# NIBB.net
KiCad netlist of a schematic drawn in EAGLE
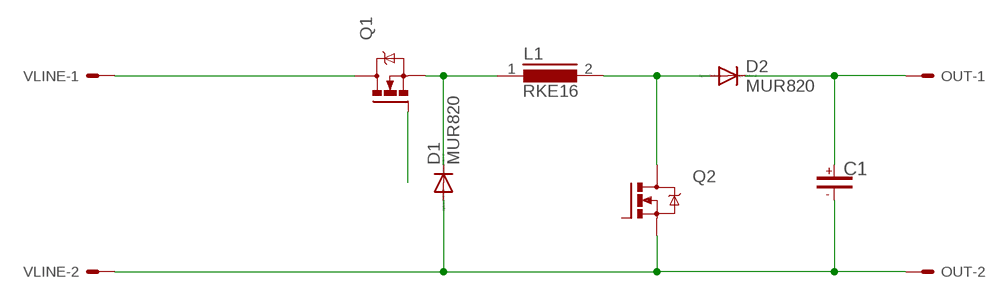
[diagram p0: schematic, sheet 1]

(export (version "E")
  (design (tool "Eeschema 10.0.6"))
  (components
    (comp (ref "C1")
      (value "CAPP-UF")
      (footprint "eagle-import:20ROUND40P")
      (libsource (lib "eagle-import") (part "CAPP-UF"))
    )
    (comp (ref "D1")
      (value "MUR820")
      (footprint "eagle-import:C221B1A")
      (libsource (lib "eagle-import") (part "MUR820"))
    )
    (comp (ref "D2")
      (value "MUR820")
      (footprint "eagle-import:C221B1A")
      (libsource (lib "eagle-import") (part "MUR820"))
    )
    (comp (ref "L1")
      (value "RKE16")
      (footprint "eagle-import:RKE16")
      (libsource (lib "eagle-import") (part "RKE16"))
    )
    (comp (ref "OUT")
      (value "22-23-2021")
      (footprint "eagle-import:22-23-2021")
      (fields (field (name "MF") "MOLEX"))
      (libsource (lib "eagle-import") (part "22-23-2021"))
    )
    (comp (ref "Q1")
      (value "IRF640")
      (footprint "eagle-import:TO220BV")
      (libsource (lib "eagle-import") (part "IRF640"))
    )
    (comp (ref "Q2")
      (value "IRF640")
      (footprint "eagle-import:TO220BV")
      (libsource (lib "eagle-import") (part "IRF640"))
    )
    (comp (ref "VLINE")
      (value "22-23-2021")
      (footprint "eagle-import:22-23-2021")
      (fields (field (name "MF") "MOLEX"))
      (libsource (lib "eagle-import") (part "22-23-2021"))
    )
  )
  (nets
    (net (code "1") (name "Net-(D1-PadC)") (class "Default")
      (node (ref "D1") (pin "C") (pinfunction "C_C") (pintype "passive"))
      (node (ref "L1") (pin "1") (pinfunction "1_1") (pintype "passive"))
      (node (ref "Q1") (pin "S") (pinfunction "S_S") (pintype "passive"))
    )
    (net (code "2") (name "Net-(D2-PadA)") (class "Default")
      (node (ref "D2") (pin "A") (pinfunction "A_A") (pintype "passive"))
      (node (ref "L1") (pin "2") (pinfunction "2_2") (pintype "passive"))
      (node (ref "Q2") (pin "D") (pinfunction "D_D") (pintype "passive"))
    )
    (net (code "3") (name "Net-(OUTA-S)") (class "Default")
      (node (ref "C1") (pin "+") (pinfunction "+_+") (pintype "passive"))
      (node (ref "D2") (pin "C") (pinfunction "C_C") (pintype "passive"))
      (node (ref "OUT") (pin "1") (pinfunction "S_1") (pintype "passive"))
    )
    (net (code "4") (name "Net-(OUTB-S)") (class "Default")
      (node (ref "C1") (pin "-") (pinfunction "-_-") (pintype "passive"))
      (node (ref "D1") (pin "A") (pinfunction "A_A") (pintype "passive"))
      (node (ref "OUT") (pin "2") (pinfunction "S_2") (pintype "passive"))
      (node (ref "Q2") (pin "S") (pinfunction "S_S") (pintype "passive"))
      (node (ref "VLINE") (pin "2") (pinfunction "S_2") (pintype "passive"))
    )
    (net (code "5") (name "Net-(VLINEA-S)") (class "Default")
      (node (ref "Q1") (pin "D") (pinfunction "D_D") (pintype "passive"))
      (node (ref "VLINE") (pin "1") (pinfunction "S_1") (pintype "passive"))
    )
    (net (code "6") (name "unconnected-(Q1-PadG)") (class "Default")
      (node (ref "Q1") (pin "G") (pinfunction "G_G") (pintype "passive"))
    )
    (net (code "7") (name "unconnected-(Q2-PadG)") (class "Default")
      (node (ref "Q2") (pin "G") (pinfunction "G_G") (pintype "passive"))
    )
  )
)
